# Power_Management.net
KiCad netlist of a schematic drawn in Altium Designer
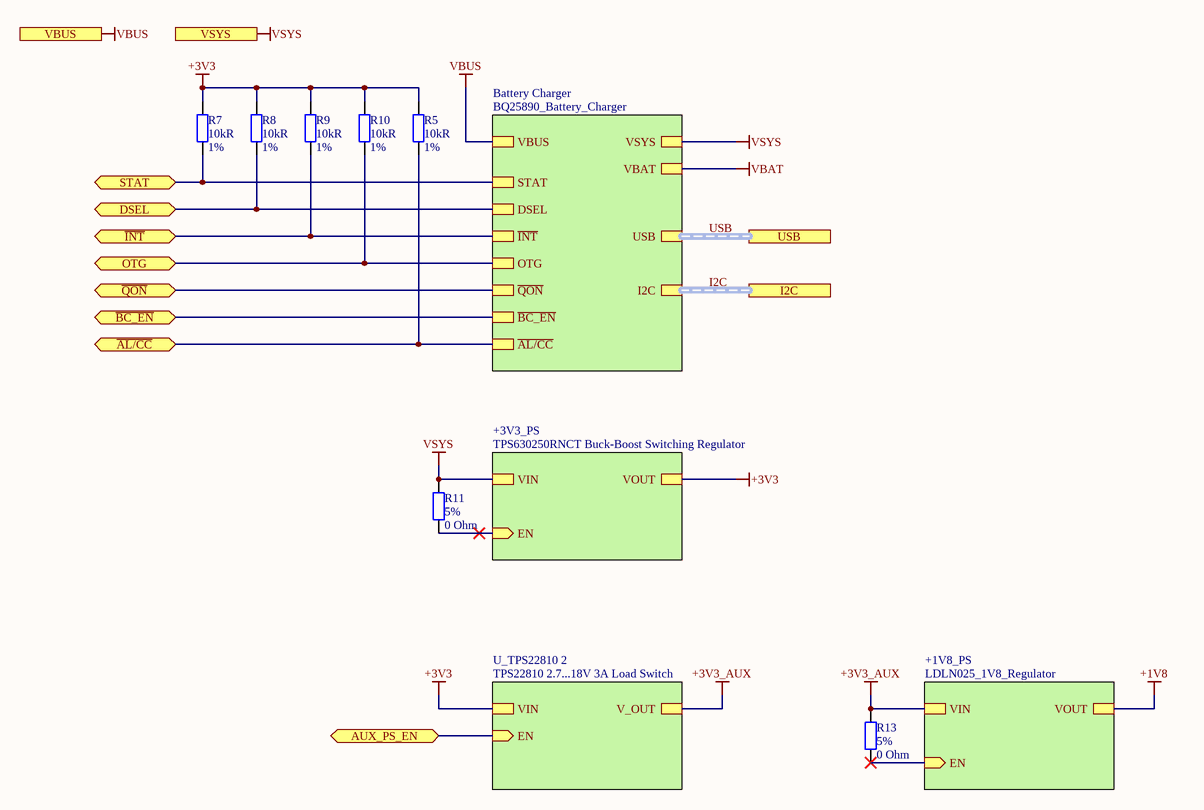
[diagram p0: Power Management.SchDoc]

(export (version "E")
  (design (tool "Eeschema 10.0.6"))
  (components
    (comp (ref "R5")
      (value "RES SMD 10K OHM 1% 1/16W 0402")
      (footprint "R0402")
      (description "10 kOhms ±1% 0.063W, 1/16W Chip Resistor 0402 (1005 Metric) Moisture Resistant Thick Film")
      (fields
        (field (name "MANUFACTURER") "Yageo")
        (field (name "MANUFACTURER PART NUMBER") "RC0402FR-0710KP")
        (field (name "RESISTANCE") "10kR")
        (field (name "TOLERANCE") "1%")
      )
      (libsource (lib "Control_Board_Model") (part "RES SMD 10K OHM 1% 1/16W 0402"))
    )
    (comp (ref "R7")
      (value "RES SMD 10K OHM 1% 1/16W 0402")
      (footprint "R0402")
      (description "10 kOhms ±1% 0.063W, 1/16W Chip Resistor 0402 (1005 Metric) Moisture Resistant Thick Film")
      (fields
        (field (name "MANUFACTURER") "Yageo")
        (field (name "MANUFACTURER PART NUMBER") "RC0402FR-0710KP")
        (field (name "RESISTANCE") "10kR")
        (field (name "TOLERANCE") "1%")
      )
      (libsource (lib "Control_Board_Model") (part "RES SMD 10K OHM 1% 1/16W 0402"))
    )
    (comp (ref "R8")
      (value "RES SMD 10K OHM 1% 1/16W 0402")
      (footprint "R0402")
      (description "10 kOhms ±1% 0.063W, 1/16W Chip Resistor 0402 (1005 Metric) Moisture Resistant Thick Film")
      (fields
        (field (name "MANUFACTURER") "Yageo")
        (field (name "MANUFACTURER PART NUMBER") "RC0402FR-0710KP")
        (field (name "RESISTANCE") "10kR")
        (field (name "TOLERANCE") "1%")
      )
      (libsource (lib "Control_Board_Model") (part "RES SMD 10K OHM 1% 1/16W 0402"))
    )
    (comp (ref "R9")
      (value "RES SMD 10K OHM 1% 1/16W 0402")
      (footprint "R0402")
      (description "10 kOhms ±1% 0.063W, 1/16W Chip Resistor 0402 (1005 Metric) Moisture Resistant Thick Film")
      (fields
        (field (name "MANUFACTURER") "Yageo")
        (field (name "MANUFACTURER PART NUMBER") "RC0402FR-0710KP")
        (field (name "RESISTANCE") "10kR")
        (field (name "TOLERANCE") "1%")
      )
      (libsource (lib "Control_Board_Model") (part "RES SMD 10K OHM 1% 1/16W 0402"))
    )
    (comp (ref "R10")
      (value "RES SMD 10K OHM 1% 1/16W 0402")
      (footprint "R0402")
      (description "10 kOhms ±1% 0.063W, 1/16W Chip Resistor 0402 (1005 Metric) Moisture Resistant Thick Film")
      (fields
        (field (name "MANUFACTURER") "Yageo")
        (field (name "MANUFACTURER PART NUMBER") "RC0402FR-0710KP")
        (field (name "RESISTANCE") "10kR")
        (field (name "TOLERANCE") "1%")
      )
      (libsource (lib "Control_Board_Model") (part "RES SMD 10K OHM 1% 1/16W 0402"))
    )
    (comp (ref "R11")
      (value "RES SMD 0 OHM JUMPER 1/16W 0402")
      (footprint "R0402")
      (description "0 Ohms Jumper 0.063W, 1/16W Chip Resistor 0402 (1005 Metric) Moisture Resistant Thick Film")
      (fields
        (field (name "MANUFACTURER") "Yageo")
        (field (name "MANUFACTURER PART NUMBER") "RC0402JR-070RL")
        (field (name "TOLERANCE") "5%")
        (field (name "RESISTANCE") "0 Ohm")
      )
      (libsource (lib "resistors_smd") (part "RES SMD 0 OHM JUMPER 1/16W 0402"))
    )
    (comp (ref "R13")
      (value "RES SMD 0 OHM JUMPER 1/16W 0402")
      (footprint "R0402")
      (description "0 Ohms Jumper 0.063W, 1/16W Chip Resistor 0402 (1005 Metric) Moisture Resistant Thick Film")
      (fields
        (field (name "MANUFACTURER") "Yageo")
        (field (name "MANUFACTURER PART NUMBER") "RC0402JR-070RL")
        (field (name "TOLERANCE") "5%")
        (field (name "RESISTANCE") "0 Ohm")
      )
      (libsource (lib "resistors_smd") (part "RES SMD 0 OHM JUMPER 1/16W 0402"))
    )
  )
  (nets
    (net (code "4") (name "+3V3") (class "Default")
      (node (ref "R10") (pin "1") (pinfunction "1_1") (pintype "passive"))
      (node (ref "R5") (pin "1") (pinfunction "1_1") (pintype "passive"))
      (node (ref "R7") (pin "1") (pinfunction "1_1") (pintype "passive"))
      (node (ref "R8") (pin "1") (pinfunction "1_1") (pintype "passive"))
      (node (ref "R9") (pin "1") (pinfunction "1_1") (pintype "passive"))
    )
    (net (code "5") (name "+3V3_AUX") (class "Default")
      (node (ref "R13") (pin "2") (pinfunction "2_2") (pintype "passive"))
    )
    (net (code "6") (name "/AL{slash}CC") (class "Default")
      (node (ref "R5") (pin "2") (pinfunction "2_2") (pintype "passive"))
    )
    (net (code "9") (name "/DSEL") (class "Default")
      (node (ref "R8") (pin "2") (pinfunction "2_2") (pintype "passive"))
    )
    (net (code "10") (name "/EN") (class "Default")
      (node (ref "R13") (pin "1") (pinfunction "1_1") (pintype "passive+no_connect"))
    )
    (net (code "11") (name "/EN_1") (class "Default")
      (node (ref "R11") (pin "1") (pinfunction "1_1") (pintype "passive"))
    )
    (net (code "12") (name "/INT") (class "Default")
      (node (ref "R9") (pin "2") (pinfunction "2_2") (pintype "passive"))
    )
    (net (code "13") (name "/OTG") (class "Default")
      (node (ref "R10") (pin "2") (pinfunction "2_2") (pintype "passive"))
    )
    (net (code "15") (name "/STAT") (class "Default")
      (node (ref "R7") (pin "2") (pinfunction "2_2") (pintype "passive"))
    )
    (net (code "20") (name "VSYS") (class "Default")
      (node (ref "R11") (pin "2") (pinfunction "2_2") (pintype "passive"))
    )
  )
)
